# T05_version11_2.net
KiCad netlist of a schematic drawn in EAGLE
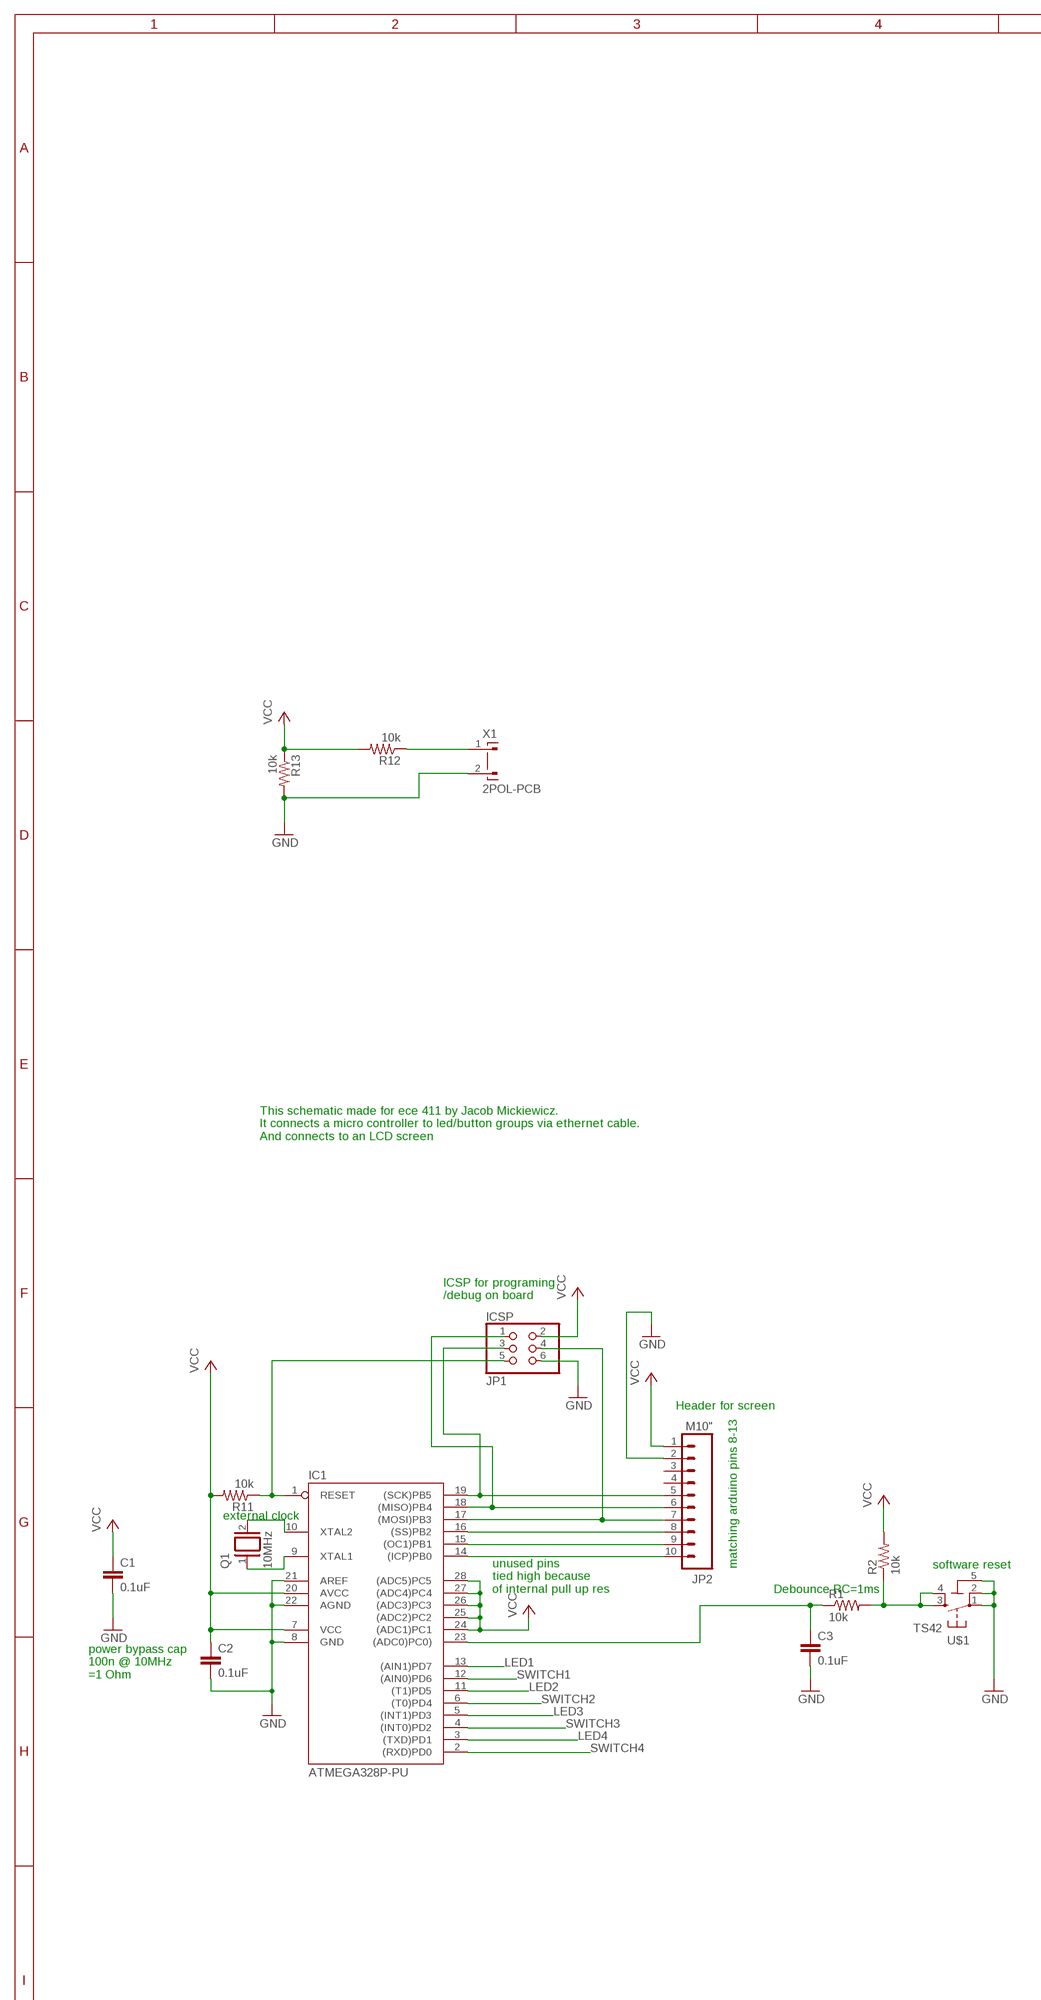
[diagram p0: schematic, sheet 1, part 1 of 2]
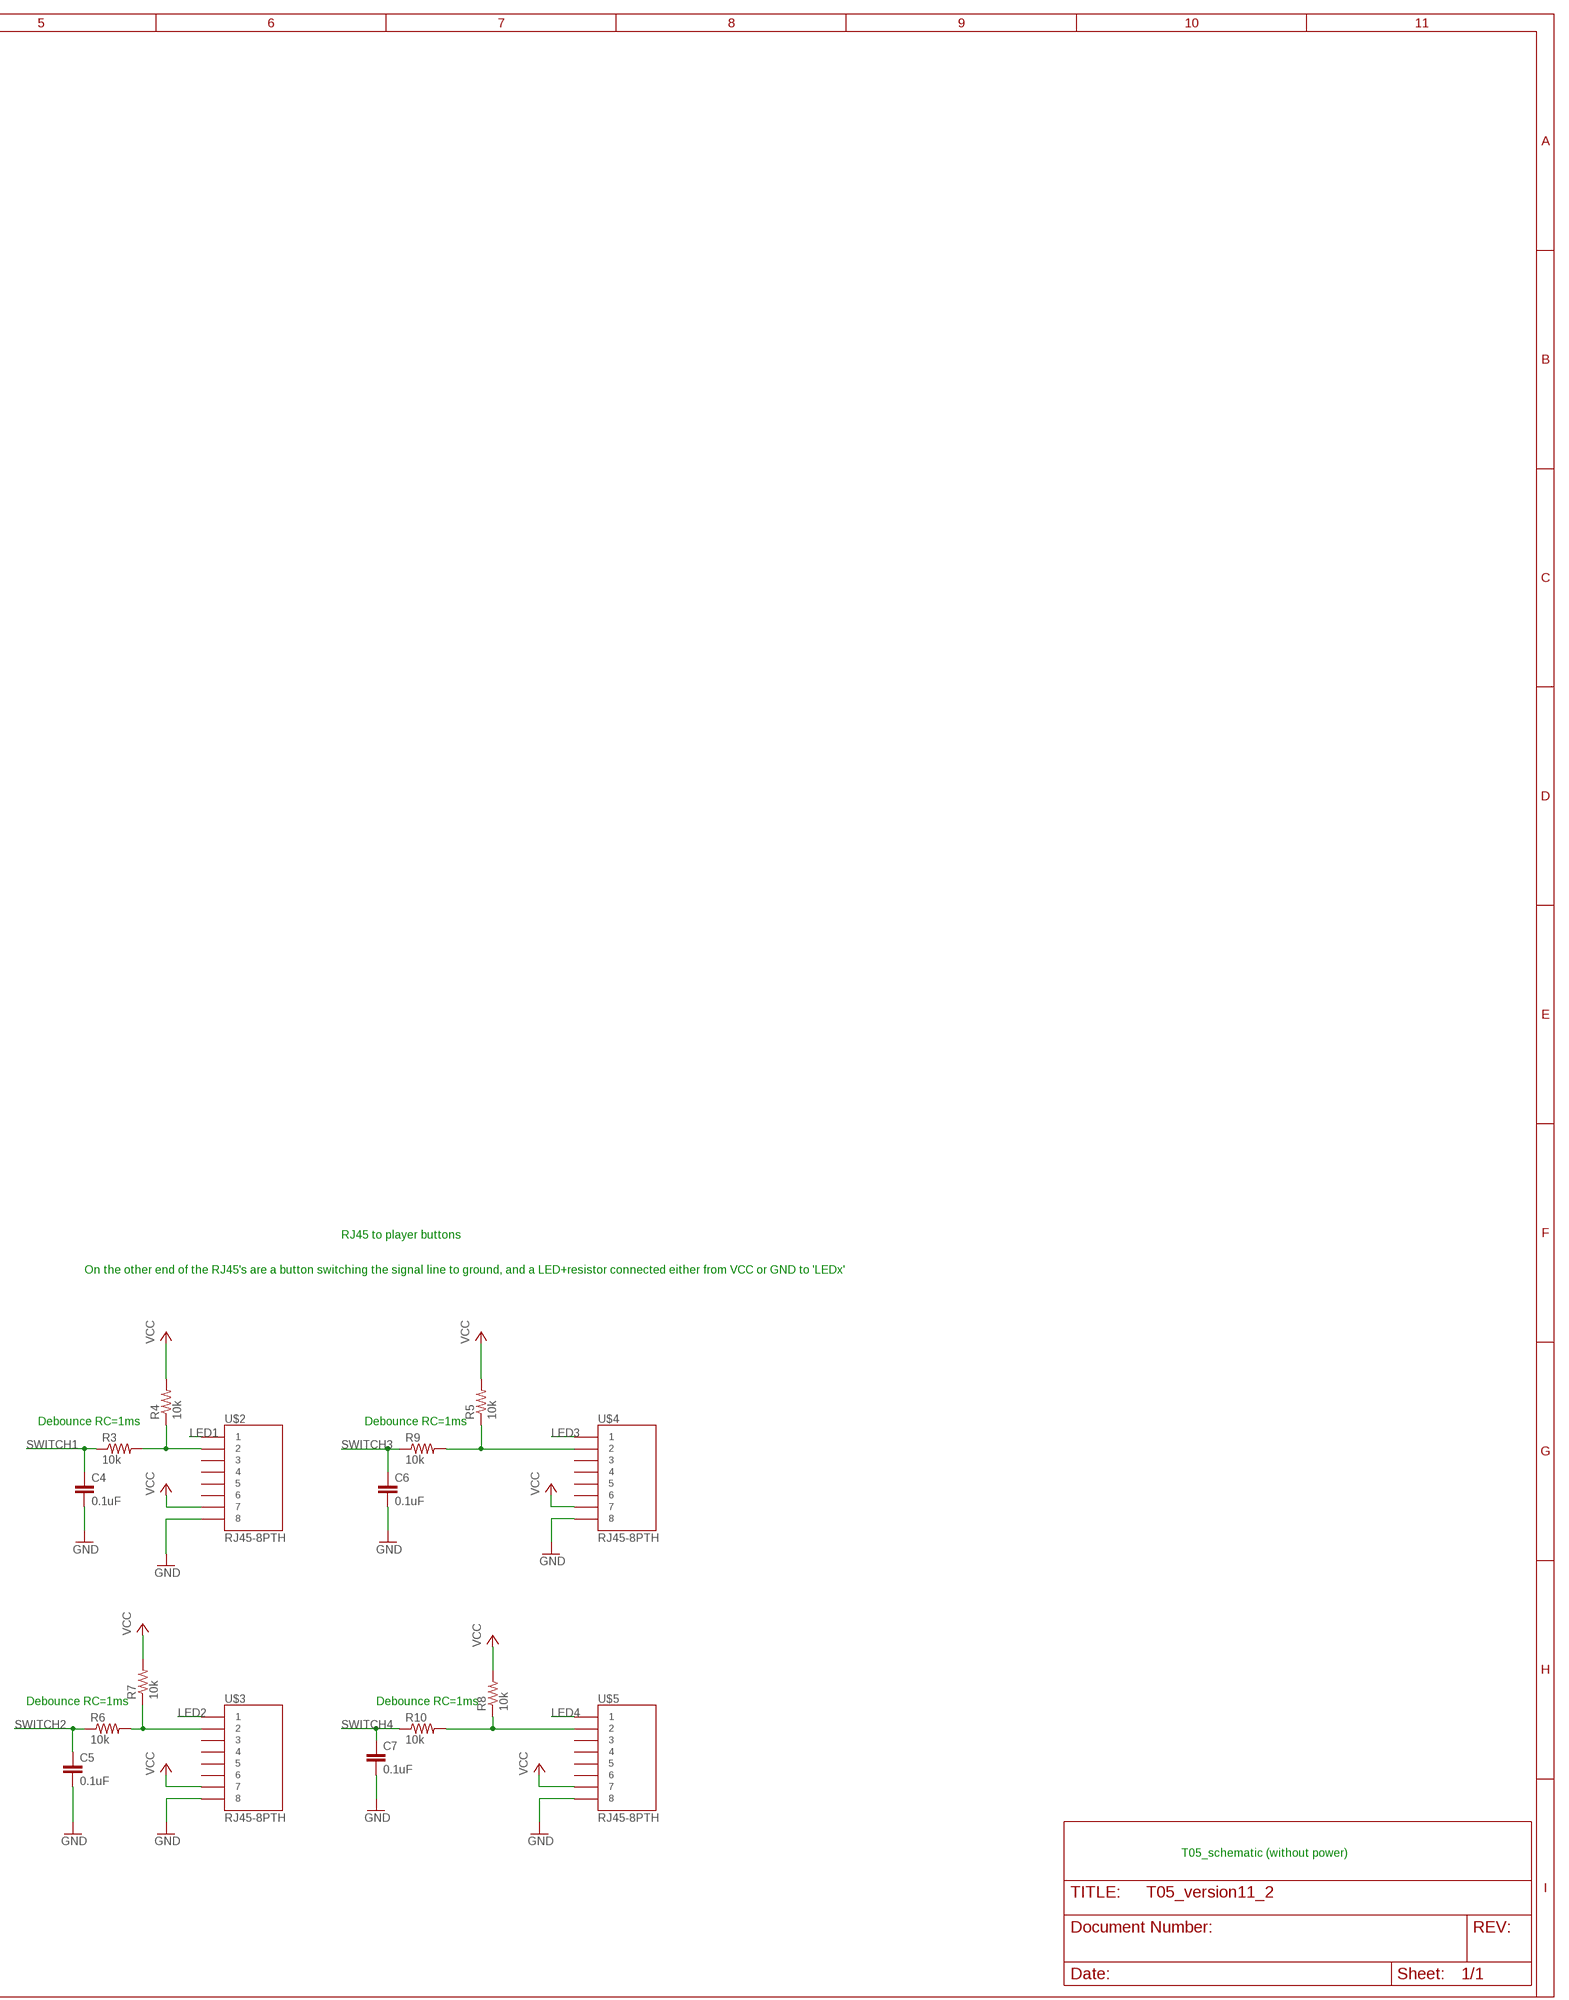
[diagram p1: schematic, sheet 1, part 2 of 2]

(export (version "E")
  (design (tool "Eeschema 10.0.6"))
  (components
    (comp (ref "C1")
      (value "0.1uF")
      (footprint "eagle-import:0603-CAP")
      (libsource (lib "eagle-import") (part "0.1UF-25V-5%(0603)"))
    )
    (comp (ref "C2")
      (value "0.1uF")
      (footprint "eagle-import:0603-CAP")
      (libsource (lib "eagle-import") (part "0.1UF-25V-5%(0603)"))
    )
    (comp (ref "C3")
      (value "0.1uF")
      (footprint "eagle-import:0603-CAP")
      (libsource (lib "eagle-import") (part "0.1UF-25V-5%(0603)"))
    )
    (comp (ref "C4")
      (value "0.1uF")
      (footprint "eagle-import:0603-CAP")
      (libsource (lib "eagle-import") (part "0.1UF-25V-5%(0603)"))
    )
    (comp (ref "C5")
      (value "0.1uF")
      (footprint "eagle-import:0603-CAP")
      (libsource (lib "eagle-import") (part "0.1UF-25V-5%(0603)"))
    )
    (comp (ref "C6")
      (value "0.1uF")
      (footprint "eagle-import:0603-CAP")
      (libsource (lib "eagle-import") (part "0.1UF-25V-5%(0603)"))
    )
    (comp (ref "C7")
      (value "0.1uF")
      (footprint "eagle-import:0603-CAP")
      (libsource (lib "eagle-import") (part "0.1UF-25V-5%(0603)"))
    )
    (comp (ref "IC1")
      (value "ATMEGA328P-PU")
      (footprint "eagle-import:DIL28-3")
      (libsource (lib "eagle-import") (part "ATMEGA328P-PU"))
    )
    (comp (ref "ICSP")
      (value "JP1")
      (footprint "eagle-import:2X03")
      (libsource (lib "eagle-import") (part "PINHD-2X3"))
    )
    (comp (ref "JP2")
      (value "M10\"")
      (footprint "eagle-import:1X10")
      (libsource (lib "eagle-import") (part "M10{dblquote}"))
    )
    (comp (ref "Q1")
      (value "10MHz")
      (footprint "eagle-import:QS")
      (libsource (lib "eagle-import") (part "XTAL/S"))
    )
    (comp (ref "R1")
      (value "10k")
      (footprint "eagle-import:0603-RES")
      (libsource (lib "eagle-import") (part "RESISTOR0603-RES"))
    )
    (comp (ref "R2")
      (value "10k")
      (footprint "eagle-import:0603-RES")
      (libsource (lib "eagle-import") (part "RESISTOR0603-RES"))
    )
    (comp (ref "R3")
      (value "10k")
      (footprint "eagle-import:0603-RES")
      (libsource (lib "eagle-import") (part "RESISTOR0603-RES"))
    )
    (comp (ref "R4")
      (value "10k")
      (footprint "eagle-import:0603-RES")
      (libsource (lib "eagle-import") (part "RESISTOR0603-RES"))
    )
    (comp (ref "R5")
      (value "10k")
      (footprint "eagle-import:0603-RES")
      (libsource (lib "eagle-import") (part "RESISTOR0603-RES"))
    )
    (comp (ref "R6")
      (value "10k")
      (footprint "eagle-import:0603-RES")
      (libsource (lib "eagle-import") (part "RESISTOR0603-RES"))
    )
    (comp (ref "R7")
      (value "10k")
      (footprint "eagle-import:0603-RES")
      (libsource (lib "eagle-import") (part "RESISTOR0603-RES"))
    )
    (comp (ref "R8")
      (value "10k")
      (footprint "eagle-import:0603-RES")
      (libsource (lib "eagle-import") (part "RESISTOR0603-RES"))
    )
    (comp (ref "R9")
      (value "10k")
      (footprint "eagle-import:0603-RES")
      (libsource (lib "eagle-import") (part "RESISTOR0603-RES"))
    )
    (comp (ref "R10")
      (value "10k")
      (footprint "eagle-import:0603-RES")
      (libsource (lib "eagle-import") (part "RESISTOR0603-RES"))
    )
    (comp (ref "R11")
      (value "10k")
      (footprint "eagle-import:0603-RES")
      (libsource (lib "eagle-import") (part "RESISTOR0603-RES"))
    )
    (comp (ref "R12")
      (value "10k")
      (footprint "eagle-import:0603-RES")
      (libsource (lib "eagle-import") (part "RESISTOR0603-RES"))
    )
    (comp (ref "R13")
      (value "10k")
      (footprint "eagle-import:0603-RES")
      (libsource (lib "eagle-import") (part "RESISTOR0603-RES"))
    )
    (comp (ref "U$1")
      (value "TS42")
      (footprint "eagle-import:TS42")
      (libsource (lib "eagle-import") (part "TS42"))
    )
    (comp (ref "U$2")
      (value "RJ45-8PTH")
      (footprint "eagle-import:RJ45-8")
      (libsource (lib "eagle-import") (part "RJ45-8PTH"))
    )
    (comp (ref "U$3")
      (value "RJ45-8PTH")
      (footprint "eagle-import:RJ45-8")
      (libsource (lib "eagle-import") (part "RJ45-8PTH"))
    )
    (comp (ref "U$4")
      (value "RJ45-8PTH")
      (footprint "eagle-import:RJ45-8")
      (libsource (lib "eagle-import") (part "RJ45-8PTH"))
    )
    (comp (ref "U$5")
      (value "RJ45-8PTH")
      (footprint "eagle-import:RJ45-8")
      (libsource (lib "eagle-import") (part "RJ45-8PTH"))
    )
    (comp (ref "X1")
      (value "2POL-PCB")
      (footprint "eagle-import:2POL-PCB")
      (libsource (lib "eagle-import") (part "2POL-PCB"))
    )
  )
  (nets
    (net (code "1") (name "/LED1") (class "Default")
      (node (ref "IC1") (pin "13") (pinfunction "(AIN1)PD7_13") (pintype "bidirectional"))
      (node (ref "U$2") (pin "1") (pinfunction "1_1") (pintype "bidirectional"))
    )
    (net (code "2") (name "/LED2") (class "Default")
      (node (ref "IC1") (pin "11") (pinfunction "(T1)PD5_11") (pintype "bidirectional"))
      (node (ref "U$3") (pin "1") (pinfunction "1_1") (pintype "bidirectional"))
    )
    (net (code "3") (name "/LED3") (class "Default")
      (node (ref "IC1") (pin "5") (pinfunction "(INT1)PD3_5") (pintype "bidirectional"))
      (node (ref "U$4") (pin "1") (pinfunction "1_1") (pintype "bidirectional"))
    )
    (net (code "4") (name "/LED4") (class "Default")
      (node (ref "IC1") (pin "3") (pinfunction "(TXD)PD1_3") (pintype "bidirectional"))
      (node (ref "U$5") (pin "1") (pinfunction "1_1") (pintype "bidirectional"))
    )
    (net (code "5") (name "/SWITCH1") (class "Default")
      (node (ref "C4") (pin "1") (pinfunction "1_1") (pintype "passive"))
      (node (ref "IC1") (pin "12") (pinfunction "(AIN0)PD6_12") (pintype "bidirectional"))
      (node (ref "R3") (pin "1") (pinfunction "1_1") (pintype "passive"))
    )
    (net (code "6") (name "/SWITCH2") (class "Default")
      (node (ref "C5") (pin "1") (pinfunction "1_1") (pintype "passive"))
      (node (ref "IC1") (pin "6") (pinfunction "(T0)PD4_6") (pintype "bidirectional"))
      (node (ref "R6") (pin "1") (pinfunction "1_1") (pintype "passive"))
    )
    (net (code "7") (name "/SWITCH3") (class "Default")
      (node (ref "C6") (pin "1") (pinfunction "1_1") (pintype "passive"))
      (node (ref "IC1") (pin "4") (pinfunction "(INT0)PD2_4") (pintype "bidirectional"))
      (node (ref "R9") (pin "1") (pinfunction "1_1") (pintype "passive"))
    )
    (net (code "8") (name "/SWITCH4") (class "Default")
      (node (ref "C7") (pin "1") (pinfunction "1_1") (pintype "passive"))
      (node (ref "IC1") (pin "2") (pinfunction "(RXD)PD0_2") (pintype "bidirectional"))
      (node (ref "R10") (pin "1") (pinfunction "1_1") (pintype "passive"))
    )
    (net (code "9") (name "GND") (class "Default")
      (node (ref "C1") (pin "2") (pinfunction "2_2") (pintype "passive"))
      (node (ref "C2") (pin "2") (pinfunction "2_2") (pintype "passive"))
      (node (ref "C3") (pin "2") (pinfunction "2_2") (pintype "passive"))
      (node (ref "C4") (pin "2") (pinfunction "2_2") (pintype "passive"))
      (node (ref "C5") (pin "2") (pinfunction "2_2") (pintype "passive"))
      (node (ref "C6") (pin "2") (pinfunction "2_2") (pintype "passive"))
      (node (ref "C7") (pin "2") (pinfunction "2_2") (pintype "passive"))
      (node (ref "IC1") (pin "21") (pinfunction "AREF_21") (pintype "passive"))
      (node (ref "IC1") (pin "22") (pinfunction "AGND_22") (pintype "power_in"))
      (node (ref "IC1") (pin "8") (pinfunction "GND_8") (pintype "power_in"))
      (node (ref "ICSP") (pin "6") (pinfunction "6_6") (pintype "passive"))
      (node (ref "JP2") (pin "2") (pinfunction "2_2") (pintype "passive"))
      (node (ref "R13") (pin "2") (pinfunction "2_2") (pintype "passive"))
      (node (ref "U$1") (pin "1") (pinfunction "1_1") (pintype "passive"))
      (node (ref "U$1") (pin "2") (pinfunction "2_2") (pintype "passive"))
      (node (ref "U$1") (pin "5") (pinfunction "5-GND_5") (pintype "power_in"))
      (node (ref "U$2") (pin "8") (pinfunction "8_8") (pintype "bidirectional"))
      (node (ref "U$3") (pin "8") (pinfunction "8_8") (pintype "bidirectional"))
      (node (ref "U$4") (pin "8") (pinfunction "8_8") (pintype "bidirectional"))
      (node (ref "U$5") (pin "8") (pinfunction "8_8") (pintype "bidirectional"))
      (node (ref "X1") (pin "2") (pinfunction "2_2") (pintype "passive"))
    )
    (net (code "10") (name "Net-(IC1-(ADC0)PC0))") (class "Default")
      (node (ref "C3") (pin "1") (pinfunction "1_1") (pintype "passive"))
      (node (ref "IC1") (pin "23") (pinfunction "(ADC0)PC0)_23") (pintype "bidirectional"))
      (node (ref "R1") (pin "1") (pinfunction "1_1") (pintype "passive"))
    )
    (net (code "11") (name "Net-(IC1-(ICP)PB0)") (class "Default")
      (node (ref "IC1") (pin "14") (pinfunction "(ICP)PB0_14") (pintype "bidirectional"))
      (node (ref "JP2") (pin "10") (pinfunction "10_10") (pintype "passive"))
    )
    (net (code "12") (name "Net-(IC1-(MISO)PB4)") (class "Default")
      (node (ref "IC1") (pin "18") (pinfunction "(MISO)PB4_18") (pintype "bidirectional"))
      (node (ref "ICSP") (pin "1") (pinfunction "1_1") (pintype "passive"))
      (node (ref "JP2") (pin "6") (pinfunction "6_6") (pintype "passive"))
    )
    (net (code "13") (name "Net-(IC1-(MOSI)PB3)") (class "Default")
      (node (ref "IC1") (pin "17") (pinfunction "(MOSI)PB3_17") (pintype "bidirectional"))
      (node (ref "ICSP") (pin "4") (pinfunction "4_4") (pintype "passive"))
      (node (ref "JP2") (pin "7") (pinfunction "7_7") (pintype "passive"))
    )
    (net (code "14") (name "Net-(IC1-(OC1)PB1)") (class "Default")
      (node (ref "IC1") (pin "15") (pinfunction "(OC1)PB1_15") (pintype "bidirectional"))
      (node (ref "JP2") (pin "9") (pinfunction "9_9") (pintype "passive"))
    )
    (net (code "15") (name "Net-(IC1-(SCK)PB5)") (class "Default")
      (node (ref "IC1") (pin "19") (pinfunction "(SCK)PB5_19") (pintype "bidirectional"))
      (node (ref "ICSP") (pin "3") (pinfunction "3_3") (pintype "passive"))
      (node (ref "JP2") (pin "5") (pinfunction "5_5") (pintype "passive"))
    )
    (net (code "16") (name "Net-(IC1-(SS)PB2)") (class "Default")
      (node (ref "IC1") (pin "16") (pinfunction "(SS)PB2_16") (pintype "bidirectional"))
      (node (ref "JP2") (pin "8") (pinfunction "8_8") (pintype "passive"))
    )
    (net (code "17") (name "Net-(IC1-RESET)") (class "Default")
      (node (ref "IC1") (pin "1") (pinfunction "RESET_1") (pintype "input"))
      (node (ref "ICSP") (pin "5") (pinfunction "5_5") (pintype "passive"))
      (node (ref "R11") (pin "1") (pinfunction "1_1") (pintype "passive"))
    )
    (net (code "18") (name "Net-(IC1-XTAL1)") (class "Default")
      (node (ref "IC1") (pin "9") (pinfunction "XTAL1_9") (pintype "bidirectional"))
      (node (ref "Q1") (pin "1") (pinfunction "1_1") (pintype "passive"))
    )
    (net (code "19") (name "Net-(IC1-XTAL2)") (class "Default")
      (node (ref "IC1") (pin "10") (pinfunction "XTAL2_10") (pintype "bidirectional"))
      (node (ref "Q1") (pin "2") (pinfunction "2_2") (pintype "passive"))
    )
    (net (code "20") (name "Net-(R1-Pad2)") (class "Default")
      (node (ref "R1") (pin "2") (pinfunction "2_2") (pintype "passive"))
      (node (ref "R2") (pin "1") (pinfunction "1_1") (pintype "passive"))
      (node (ref "U$1") (pin "3") (pinfunction "3_3") (pintype "passive"))
      (node (ref "U$1") (pin "4") (pinfunction "4_4") (pintype "passive"))
    )
    (net (code "21") (name "Net-(R3-Pad2)") (class "Default")
      (node (ref "R3") (pin "2") (pinfunction "2_2") (pintype "passive"))
      (node (ref "R4") (pin "1") (pinfunction "1_1") (pintype "passive"))
      (node (ref "U$2") (pin "2") (pinfunction "2_2") (pintype "bidirectional"))
    )
    (net (code "22") (name "Net-(R5-Pad1)") (class "Default")
      (node (ref "R5") (pin "1") (pinfunction "1_1") (pintype "passive"))
      (node (ref "R9") (pin "2") (pinfunction "2_2") (pintype "passive"))
      (node (ref "U$4") (pin "2") (pinfunction "2_2") (pintype "bidirectional"))
    )
    (net (code "23") (name "Net-(R6-Pad2)") (class "Default")
      (node (ref "R6") (pin "2") (pinfunction "2_2") (pintype "passive"))
      (node (ref "R7") (pin "1") (pinfunction "1_1") (pintype "passive"))
      (node (ref "U$3") (pin "2") (pinfunction "2_2") (pintype "bidirectional"))
    )
    (net (code "24") (name "Net-(R10-Pad2)") (class "Default")
      (node (ref "R10") (pin "2") (pinfunction "2_2") (pintype "passive"))
      (node (ref "R8") (pin "1") (pinfunction "1_1") (pintype "passive"))
      (node (ref "U$5") (pin "2") (pinfunction "2_2") (pintype "bidirectional"))
    )
    (net (code "25") (name "Net-(R12-Pad1)") (class "Default")
      (node (ref "R12") (pin "1") (pinfunction "1_1") (pintype "passive"))
      (node (ref "X1") (pin "1") (pinfunction "1_1") (pintype "passive"))
    )
    (net (code "26") (name "VCC") (class "Default")
      (node (ref "C1") (pin "1") (pinfunction "1_1") (pintype "passive"))
      (node (ref "C2") (pin "1") (pinfunction "1_1") (pintype "passive"))
      (node (ref "IC1") (pin "20") (pinfunction "AVCC_20") (pintype "power_in"))
      (node (ref "IC1") (pin "24") (pinfunction "(ADC1)PC1_24") (pintype "bidirectional"))
      (node (ref "IC1") (pin "25") (pinfunction "(ADC2)PC2_25") (pintype "bidirectional"))
      (node (ref "IC1") (pin "26") (pinfunction "(ADC3)PC3_26") (pintype "bidirectional"))
      (node (ref "IC1") (pin "27") (pinfunction "(ADC4)PC4_27") (pintype "bidirectional"))
      (node (ref "IC1") (pin "28") (pinfunction "(ADC5)PC5_28") (pintype "bidirectional"))
      (node (ref "IC1") (pin "7") (pinfunction "VCC_7") (pintype "power_in"))
      (node (ref "ICSP") (pin "2") (pinfunction "2_2") (pintype "passive"))
      (node (ref "JP2") (pin "1") (pinfunction "1_1") (pintype "passive"))
      (node (ref "R11") (pin "2") (pinfunction "2_2") (pintype "passive"))
      (node (ref "R12") (pin "2") (pinfunction "2_2") (pintype "passive"))
      (node (ref "R13") (pin "1") (pinfunction "1_1") (pintype "passive"))
      (node (ref "R2") (pin "2") (pinfunction "2_2") (pintype "passive"))
      (node (ref "R4") (pin "2") (pinfunction "2_2") (pintype "passive"))
      (node (ref "R5") (pin "2") (pinfunction "2_2") (pintype "passive"))
      (node (ref "R7") (pin "2") (pinfunction "2_2") (pintype "passive"))
      (node (ref "R8") (pin "2") (pinfunction "2_2") (pintype "passive"))
      (node (ref "U$2") (pin "7") (pinfunction "7_7") (pintype "bidirectional"))
      (node (ref "U$3") (pin "7") (pinfunction "7_7") (pintype "bidirectional"))
      (node (ref "U$4") (pin "7") (pinfunction "7_7") (pintype "bidirectional"))
      (node (ref "U$5") (pin "7") (pinfunction "7_7") (pintype "bidirectional"))
    )
    (net (code "27") (name "unconnected-(JP2-Pad3)") (class "Default")
      (node (ref "JP2") (pin "3") (pinfunction "3_3") (pintype "passive"))
    )
    (net (code "28") (name "unconnected-(JP2-Pad4)") (class "Default")
      (node (ref "JP2") (pin "4") (pinfunction "4_4") (pintype "passive"))
    )
    (net (code "29") (name "unconnected-(U$2-Pad3)") (class "Default")
      (node (ref "U$2") (pin "3") (pinfunction "3_3") (pintype "bidirectional"))
    )
    (net (code "30") (name "unconnected-(U$2-Pad4)") (class "Default")
      (node (ref "U$2") (pin "4") (pinfunction "4_4") (pintype "bidirectional"))
    )
    (net (code "31") (name "unconnected-(U$2-Pad5)") (class "Default")
      (node (ref "U$2") (pin "5") (pinfunction "5_5") (pintype "bidirectional"))
    )
    (net (code "32") (name "unconnected-(U$2-Pad6)") (class "Default")
      (node (ref "U$2") (pin "6") (pinfunction "6_6") (pintype "bidirectional"))
    )
    (net (code "33") (name "unconnected-(U$3-Pad3)") (class "Default")
      (node (ref "U$3") (pin "3") (pinfunction "3_3") (pintype "bidirectional"))
    )
    (net (code "34") (name "unconnected-(U$3-Pad4)") (class "Default")
      (node (ref "U$3") (pin "4") (pinfunction "4_4") (pintype "bidirectional"))
    )
    (net (code "35") (name "unconnected-(U$3-Pad5)") (class "Default")
      (node (ref "U$3") (pin "5") (pinfunction "5_5") (pintype "bidirectional"))
    )
    (net (code "36") (name "unconnected-(U$3-Pad6)") (class "Default")
      (node (ref "U$3") (pin "6") (pinfunction "6_6") (pintype "bidirectional"))
    )
    (net (code "37") (name "unconnected-(U$4-Pad3)") (class "Default")
      (node (ref "U$4") (pin "3") (pinfunction "3_3") (pintype "bidirectional"))
    )
    (net (code "38") (name "unconnected-(U$4-Pad4)") (class "Default")
      (node (ref "U$4") (pin "4") (pinfunction "4_4") (pintype "bidirectional"))
    )
    (net (code "39") (name "unconnected-(U$4-Pad5)") (class "Default")
      (node (ref "U$4") (pin "5") (pinfunction "5_5") (pintype "bidirectional"))
    )
    (net (code "40") (name "unconnected-(U$4-Pad6)") (class "Default")
      (node (ref "U$4") (pin "6") (pinfunction "6_6") (pintype "bidirectional"))
    )
    (net (code "41") (name "unconnected-(U$5-Pad3)") (class "Default")
      (node (ref "U$5") (pin "3") (pinfunction "3_3") (pintype "bidirectional"))
    )
    (net (code "42") (name "unconnected-(U$5-Pad4)") (class "Default")
      (node (ref "U$5") (pin "4") (pinfunction "4_4") (pintype "bidirectional"))
    )
    (net (code "43") (name "unconnected-(U$5-Pad5)") (class "Default")
      (node (ref "U$5") (pin "5") (pinfunction "5_5") (pintype "bidirectional"))
    )
    (net (code "44") (name "unconnected-(U$5-Pad6)") (class "Default")
      (node (ref "U$5") (pin "6") (pinfunction "6_6") (pintype "bidirectional"))
    )
  )
)
